# canSlaveV04_Hoch.net
KiCad netlist of a schematic drawn in EAGLE
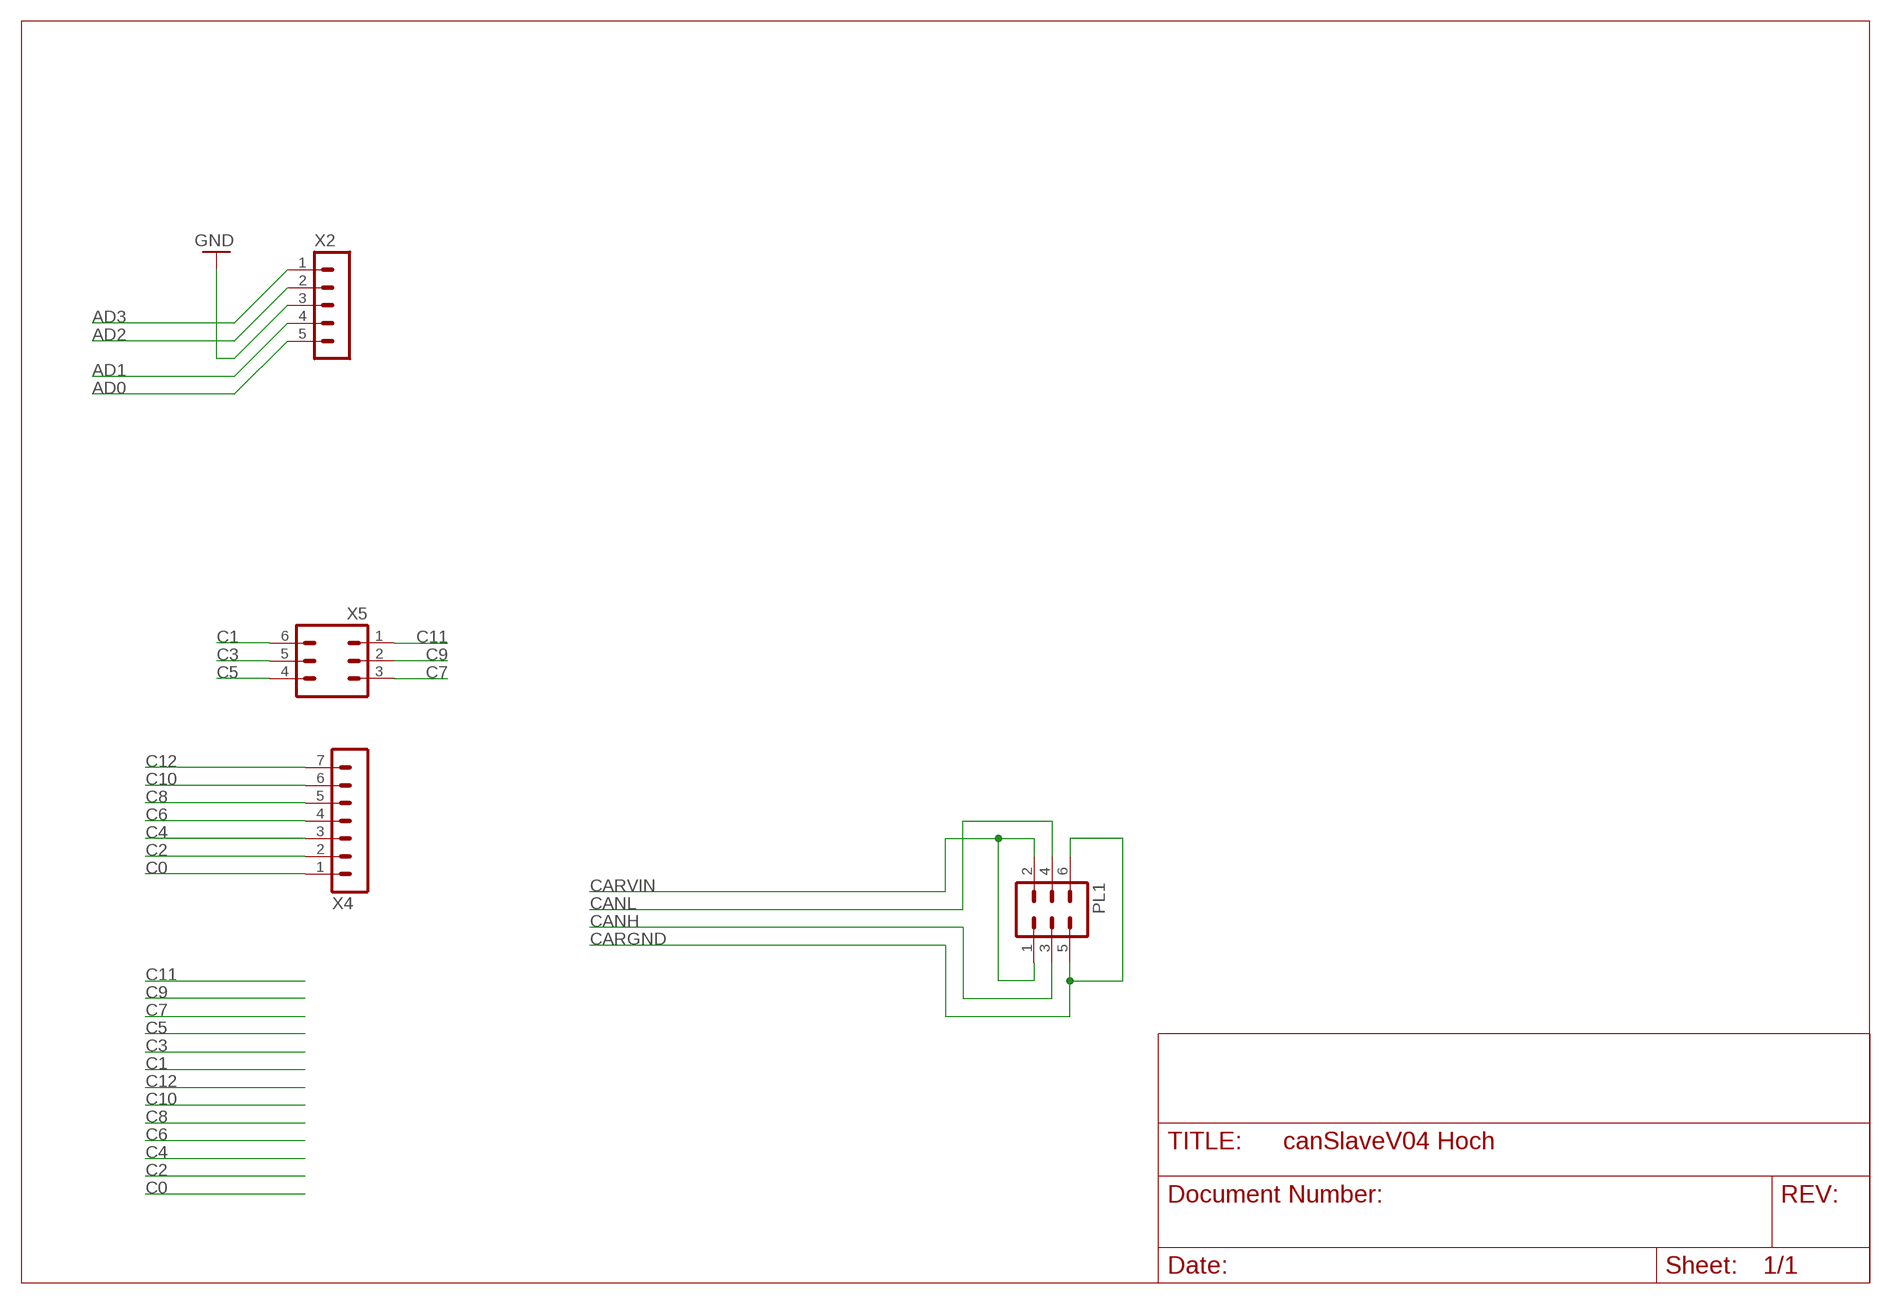
[diagram p0: schematic, sheet 1]

(export (version "E")
  (design (tool "Eeschema 10.0.6"))
  (components
    (comp (ref "PL1")
      (value "06V")
      (footprint "eagle-import:06V")
      (libsource (lib "eagle-import") (part "06V"))
    )
    (comp (ref "X2")
      (value "HEADER_POS5_43650-0515")
      (footprint "eagle-import:43650-0515")
      (libsource (lib "eagle-import") (part "HEADER_POS5_?43650-0515"))
    )
    (comp (ref "X4")
      (value "HEADER_POS7_43650-0715")
      (footprint "eagle-import:43650-0715")
      (libsource (lib "eagle-import") (part "HEADER_POS7_?43650-0715"))
    )
    (comp (ref "X5")
      (value "HEADER_POS6_43650-0615")
      (footprint "eagle-import:43650-0615")
      (libsource (lib "eagle-import") (part "HEADER_POS6_?43650-0615"))
    )
  )
  (nets
    (net (code "1") (name "/AD0") (class "Default")
      (node (ref "X2") (pin "5") (pinfunction "5_5") (pintype "passive"))
    )
    (net (code "2") (name "/AD1") (class "Default")
      (node (ref "X2") (pin "4") (pinfunction "4_4") (pintype "passive"))
    )
    (net (code "3") (name "/AD2") (class "Default")
      (node (ref "X2") (pin "2") (pinfunction "2_2") (pintype "passive"))
    )
    (net (code "4") (name "/AD3") (class "Default")
      (node (ref "X2") (pin "1") (pinfunction "1_1") (pintype "passive"))
    )
    (net (code "5") (name "/C0") (class "Default")
      (node (ref "X4") (pin "1") (pinfunction "1_1") (pintype "passive"))
    )
    (net (code "6") (name "/C1") (class "Default")
      (node (ref "X5") (pin "6") (pinfunction "6_6") (pintype "passive"))
    )
    (net (code "7") (name "/C2") (class "Default")
      (node (ref "X4") (pin "2") (pinfunction "2_2") (pintype "passive"))
    )
    (net (code "8") (name "/C3") (class "Default")
      (node (ref "X5") (pin "5") (pinfunction "5_5") (pintype "passive"))
    )
    (net (code "9") (name "/C4") (class "Default")
      (node (ref "X4") (pin "3") (pinfunction "3_3") (pintype "passive"))
    )
    (net (code "10") (name "/C5") (class "Default")
      (node (ref "X5") (pin "4") (pinfunction "4_4") (pintype "passive"))
    )
    (net (code "11") (name "/C6") (class "Default")
      (node (ref "X4") (pin "4") (pinfunction "4_4") (pintype "passive"))
    )
    (net (code "12") (name "/C7") (class "Default")
      (node (ref "X5") (pin "3") (pinfunction "3_3") (pintype "passive"))
    )
    (net (code "13") (name "/C8") (class "Default")
      (node (ref "X4") (pin "5") (pinfunction "5_5") (pintype "passive"))
    )
    (net (code "14") (name "/C9") (class "Default")
      (node (ref "X5") (pin "2") (pinfunction "2_2") (pintype "passive"))
    )
    (net (code "15") (name "/C10") (class "Default")
      (node (ref "X4") (pin "6") (pinfunction "6_6") (pintype "passive"))
    )
    (net (code "16") (name "/C11") (class "Default")
      (node (ref "X5") (pin "1") (pinfunction "1_1") (pintype "passive"))
    )
    (net (code "17") (name "/C12") (class "Default")
      (node (ref "X4") (pin "7") (pinfunction "7_7") (pintype "passive"))
    )
    (net (code "18") (name "/CANH") (class "Default")
      (node (ref "PL1") (pin "3") (pinfunction "3_3") (pintype "passive"))
    )
    (net (code "19") (name "/CANL") (class "Default")
      (node (ref "PL1") (pin "4") (pinfunction "4_4") (pintype "passive"))
    )
    (net (code "20") (name "/CARGND") (class "Default")
      (node (ref "PL1") (pin "5") (pinfunction "5_5") (pintype "passive"))
      (node (ref "PL1") (pin "6") (pinfunction "6_6") (pintype "passive"))
    )
    (net (code "21") (name "/CARVIN") (class "Default")
      (node (ref "PL1") (pin "1") (pinfunction "1_1") (pintype "passive"))
      (node (ref "PL1") (pin "2") (pinfunction "2_2") (pintype "passive"))
    )
    (net (code "22") (name "GND") (class "Default")
      (node (ref "X2") (pin "3") (pinfunction "3_3") (pintype "passive"))
    )
  )
)
